# DM3370_IMX214.net
KiCad netlist of a schematic drawn in Altium Designer
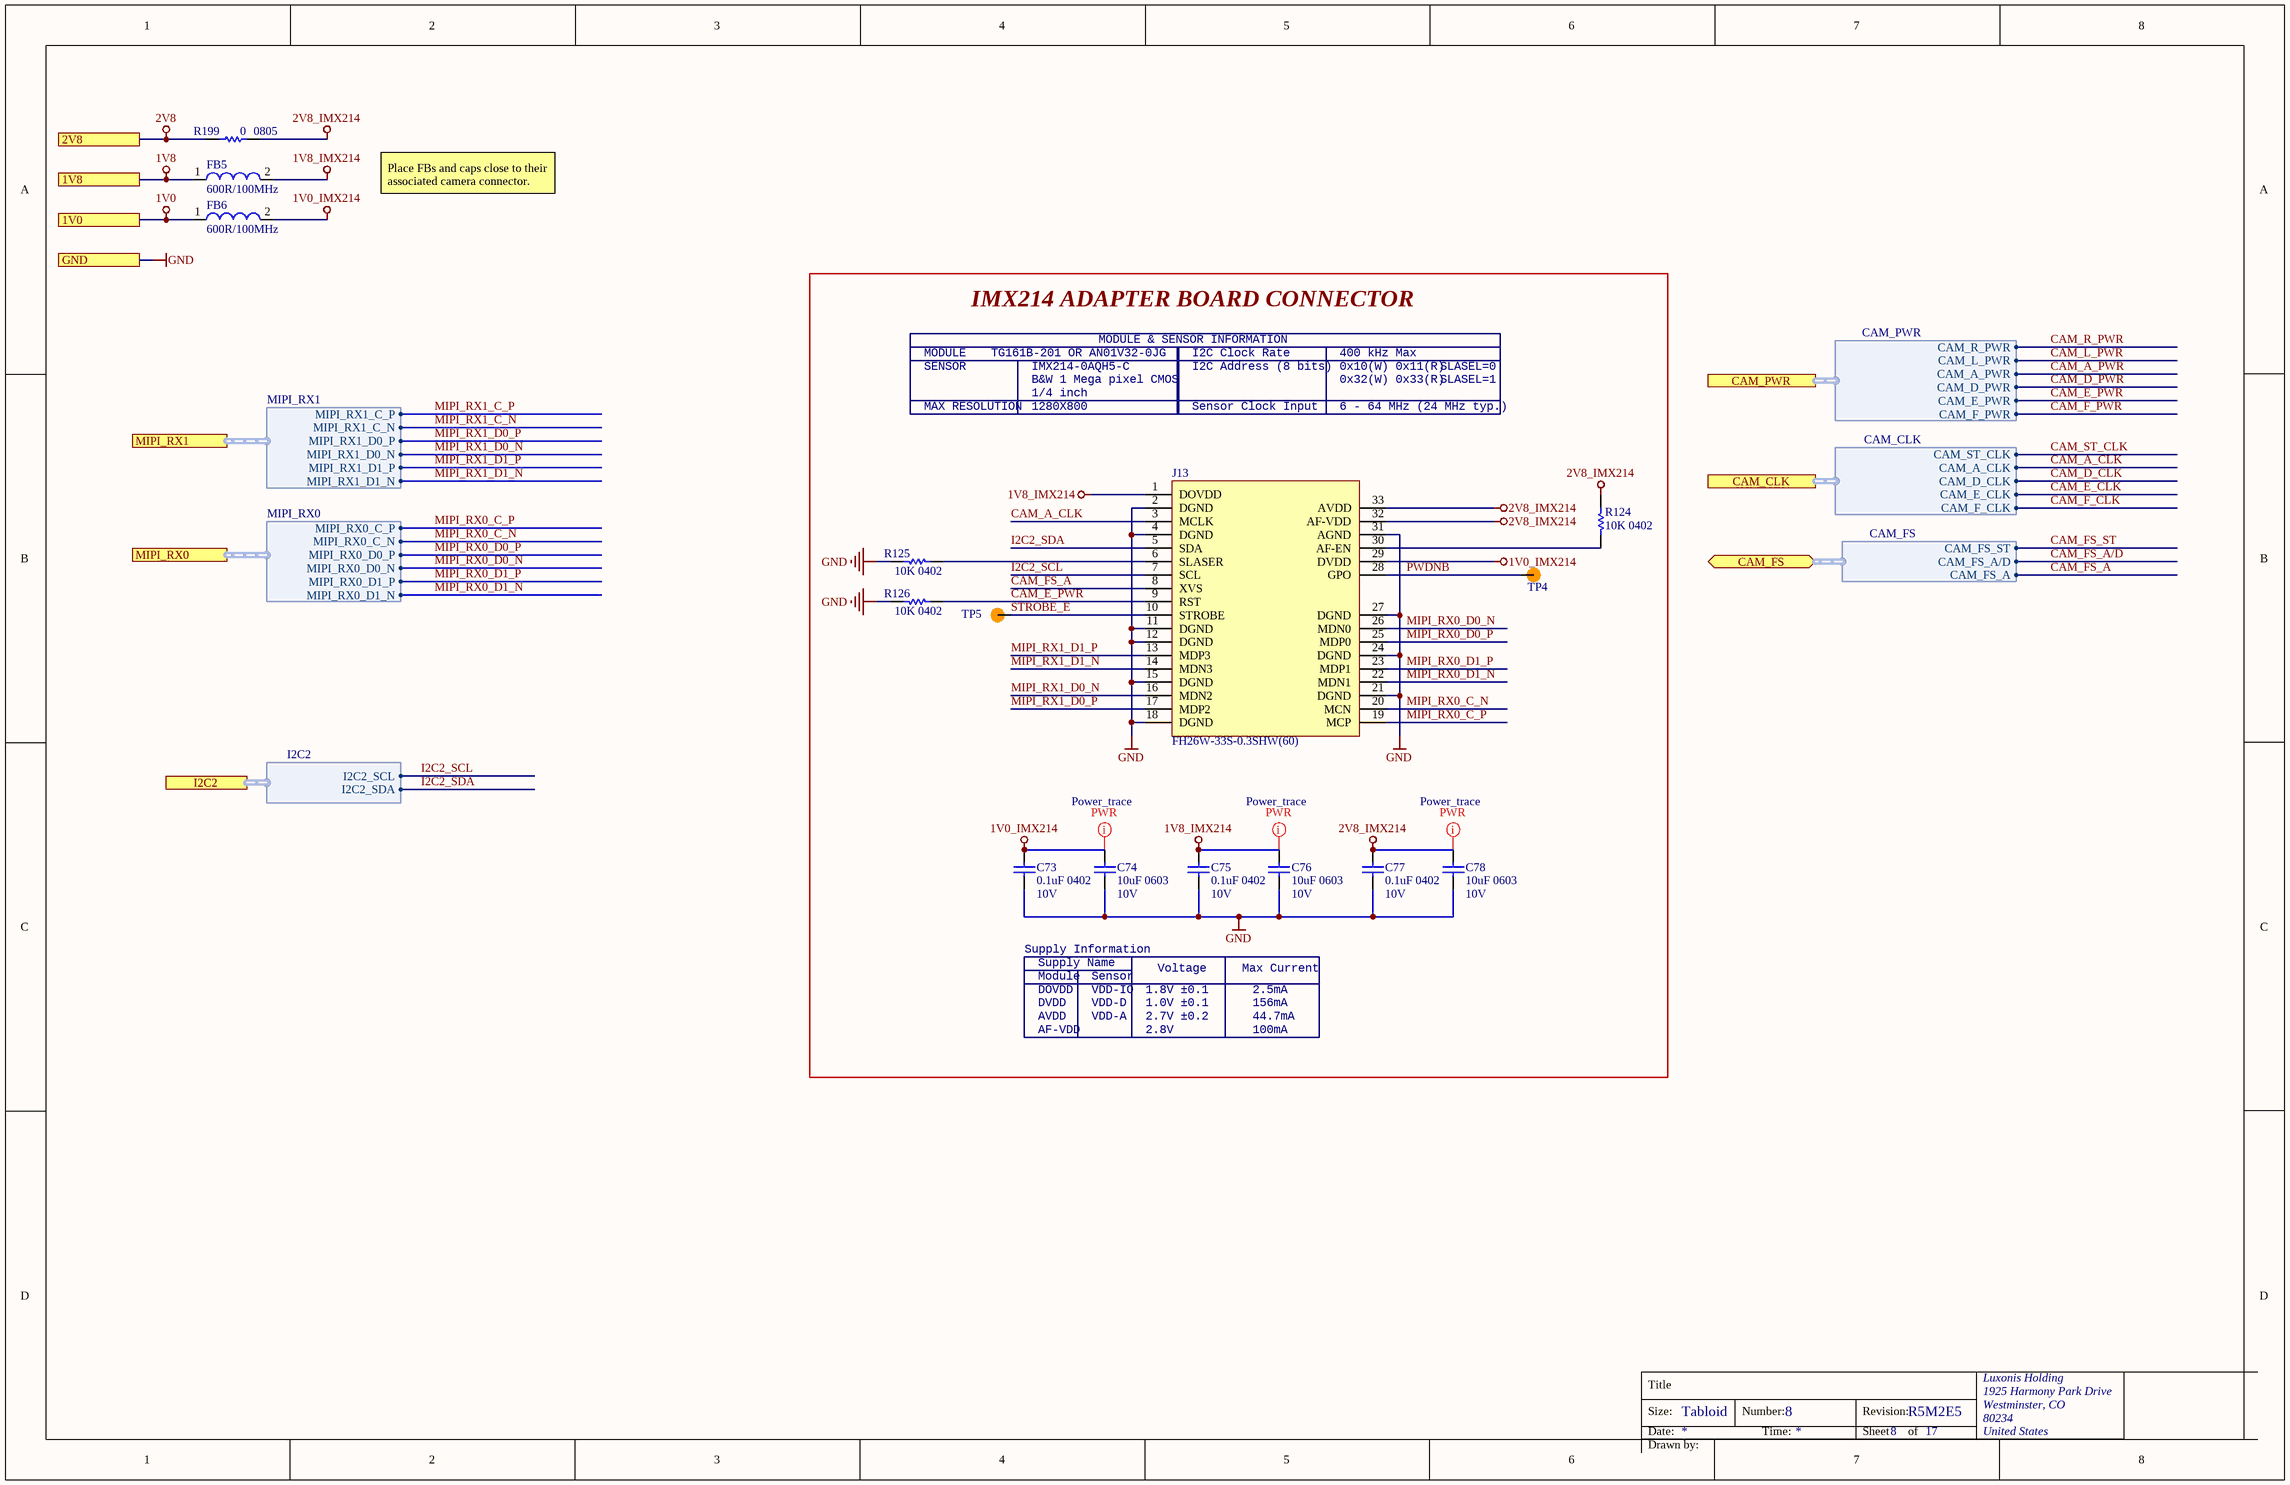
[diagram p0: DM3370_IMX214.SchDoc]

(export (version "E")
  (design (tool "Eeschema 10.0.6"))
  (components
    (comp (ref "C73")
      (value "0.1uF 0402")
      (footprint "CAP_Altium_Vault_Generic:CAPC0402(1005)70_L")
      (description "CAP CER 0.1UF 10V X7R 0402 5%")
      (fields (field (name "TOLERANCE") "5%") (field (name "VOLTAGE RATING") "10V"))
      (libsource (lib "LuxonisMaster") (part "GRM155R71A104JA01D"))
    )
    (comp (ref "C74")
      (value "10uF 0603")
      (footprint "CAP_Altium_Vault_Generic:CAPC0603(1608)100_L")
      (description "CAP CER 10UF 10V X5R 0603 20%")
      (fields (field (name "TOLERANCE") "20%") (field (name "VOLTAGE RATING") "10V"))
      (libsource (lib "LuxonisMaster") (part "GRM188R61A106ME69D"))
    )
    (comp (ref "C75")
      (value "0.1uF 0402")
      (footprint "CAP_Altium_Vault_Generic:CAPC0402(1005)70_L")
      (description "CAP CER 0.1UF 10V X7R 0402 5%")
      (fields (field (name "TOLERANCE") "5%") (field (name "VOLTAGE RATING") "10V"))
      (libsource (lib "LuxonisMaster") (part "GRM155R71A104JA01D"))
    )
    (comp (ref "C76")
      (value "10uF 0603")
      (footprint "CAP_Altium_Vault_Generic:CAPC0603(1608)100_L")
      (description "CAP CER 10UF 10V X5R 0603 20%")
      (fields (field (name "TOLERANCE") "20%") (field (name "VOLTAGE RATING") "10V"))
      (libsource (lib "LuxonisMaster") (part "GRM188R61A106ME69D"))
    )
    (comp (ref "C77")
      (value "0.1uF 0402")
      (footprint "CAP_Altium_Vault_Generic:CAPC0402(1005)70_L")
      (description "CAP CER 0.1UF 10V X7R 0402 5%")
      (fields (field (name "TOLERANCE") "5%") (field (name "VOLTAGE RATING") "10V"))
      (libsource (lib "LuxonisMaster") (part "GRM155R71A104JA01D"))
    )
    (comp (ref "C78")
      (value "10uF 0603")
      (footprint "CAP_Altium_Vault_Generic:CAPC0603(1608)100_L")
      (description "CAP CER 10UF 10V X5R 0603 20%")
      (fields (field (name "TOLERANCE") "20%") (field (name "VOLTAGE RATING") "10V"))
      (libsource (lib "LuxonisMaster") (part "GRM188R61A106ME69D"))
    )
    (comp (ref "FB5")
      (value "600R/100MHz")
      (footprint "LuxonisMaster:2508056017Y2")
      (description "FERRITE BEAD, 0.1OHM, 2A, 0805, 600R/100MHz")
      (fields (field (name "TOLERANCE") "25%"))
      (libsource (lib "LuxonisMaster") (part "2508056017Y2"))
    )
    (comp (ref "FB6")
      (value "600R/100MHz")
      (footprint "LuxonisMaster:2508056017Y2")
      (description "FERRITE BEAD, 0.1OHM, 2A, 0805, 600R/100MHz")
      (fields (field (name "TOLERANCE") "25%"))
      (libsource (lib "LuxonisMaster") (part "2508056017Y2"))
    )
    (comp (ref "J13")
      (value "FH26W-33S-0.3SHW(60)")
      (footprint "FH26W-33S-0.3SHW(60)")
      (description "FFC/FPC Connector, 33 Contact(s), 1 Row(s), Female, Right Angle, Surface Mount Terminal")
      (libsource (lib "Luxonis LLC") (part "FH26W-33S-0.3SHW(60)"))
    )
    (comp (ref "R124")
      (value "10K 0402")
      (footprint "RES_Altium_Vault_Generic:RESC0402(1005)_L")
      (fields (field (name "TOLERANCE") "1%"))
      (libsource (lib "LuxonisMaster") (part "RC0402FR-1310KL"))
    )
    (comp (ref "R125")
      (value "10K 0402")
      (footprint "RES_Altium_Vault_Generic:RESC0402(1005)_L")
      (fields (field (name "TOLERANCE") "1%"))
      (libsource (lib "LuxonisMaster") (part "RC0402FR-1310KL"))
    )
    (comp (ref "R126")
      (value "10K 0402")
      (footprint "RES_Altium_Vault_Generic:RESC0402(1005)_L")
      (fields (field (name "TOLERANCE") "1%"))
      (libsource (lib "LuxonisMaster") (part "RC0402FR-1310KL"))
    )
    (comp (ref "R199")
      (value "0")
      (footprint "RESC0805(2012)_L")
      (description "RES SMD 0 OHM 1% 1/8W 0805")
      (fields (field (name "CASE/PACKAGE") "0805") (field (name "Comment") "CRCW08050000Z0EA"))
      (libsource (lib "Luxonis LLC") (part "Default resistor symbol"))
    )
    (comp (ref "TP4")
      (value "TP100_200_NS")
      (footprint "LuxonisMaster:TP100_200_NS")
      (libsource (lib "LuxonisMaster") (part "TEST_POINT"))
    )
    (comp (ref "TP5")
      (value "TP100_200_NS")
      (footprint "LuxonisMaster:TP100_200_NS")
      (libsource (lib "LuxonisMaster") (part "TEST_POINT"))
    )
  )
  (nets
    (net (code "7") (name "/CAM_A_CLK") (class "Default")
      (node (ref "J13") (pin "3") (pinfunction "MCLK_3") (pintype "passive"))
    )
    (net (code "12") (name "/CAM_E_PWR") (class "Default")
      (node (ref "J13") (pin "9") (pinfunction "RST_9") (pintype "passive"))
      (node (ref "R126") (pin "1") (pinfunction "1_1") (pintype "passive"))
    )
    (net (code "13") (name "/CAM_FS_A") (class "Default")
      (node (ref "J13") (pin "8") (pinfunction "XVS_8") (pintype "passive"))
    )
    (net (code "21") (name "/I2C2_SCL") (class "Default")
      (node (ref "J13") (pin "7") (pinfunction "SCL_7") (pintype "passive"))
    )
    (net (code "22") (name "/I2C2_SDA") (class "Default")
      (node (ref "J13") (pin "5") (pinfunction "SDA_5") (pintype "passive"))
    )
    (net (code "23") (name "/MIPI_RX0_C_N") (class "Default")
      (node (ref "J13") (pin "20") (pinfunction "MCN_20") (pintype "passive"))
    )
    (net (code "24") (name "/MIPI_RX0_C_P") (class "Default")
      (node (ref "J13") (pin "19") (pinfunction "MCP_19") (pintype "passive"))
    )
    (net (code "25") (name "/MIPI_RX0_D0_N") (class "Default")
      (node (ref "J13") (pin "26") (pinfunction "MDN0_26") (pintype "passive"))
    )
    (net (code "26") (name "/MIPI_RX0_D0_P") (class "Default")
      (node (ref "J13") (pin "25") (pinfunction "MDP0_25") (pintype "passive"))
    )
    (net (code "27") (name "/MIPI_RX0_D1_N") (class "Default")
      (node (ref "J13") (pin "22") (pinfunction "MDN1_22") (pintype "passive"))
    )
    (net (code "28") (name "/MIPI_RX0_D1_P") (class "Default")
      (node (ref "J13") (pin "23") (pinfunction "MDP1_23") (pintype "passive"))
    )
    (net (code "31") (name "/MIPI_RX1_D0_N") (class "Default")
      (node (ref "J13") (pin "16") (pinfunction "MDN2_16") (pintype "passive"))
    )
    (net (code "32") (name "/MIPI_RX1_D0_P") (class "Default")
      (node (ref "J13") (pin "17") (pinfunction "MDP2_17") (pintype "passive"))
    )
    (net (code "33") (name "/MIPI_RX1_D1_N") (class "Default")
      (node (ref "J13") (pin "14") (pinfunction "MDN3_14") (pintype "passive"))
    )
    (net (code "34") (name "/MIPI_RX1_D1_P") (class "Default")
      (node (ref "J13") (pin "13") (pinfunction "MDP3_13") (pintype "passive"))
    )
    (net (code "35") (name "/PWDNB") (class "Default")
      (node (ref "J13") (pin "28") (pinfunction "GPO_28") (pintype "passive"))
      (node (ref "TP4") (pin "1") (pintype "passive"))
    )
    (net (code "36") (name "/STROBE_E") (class "Default")
      (node (ref "J13") (pin "10") (pinfunction "STROBE_10") (pintype "passive"))
      (node (ref "TP5") (pin "1") (pintype "passive"))
    )
    (net (code "43") (name "1V0") (class "Default")
      (node (ref "FB6") (pin "1") (pinfunction "1_1") (pintype "passive"))
    )
    (net (code "44") (name "1V0_IMX214") (class "Default")
      (node (ref "C73") (pin "2") (pinfunction "2_2") (pintype "passive"))
      (node (ref "C74") (pin "2") (pinfunction "2_2") (pintype "passive"))
      (node (ref "FB6") (pin "2") (pinfunction "2_2") (pintype "passive"))
      (node (ref "J13") (pin "29") (pinfunction "DVDD_29") (pintype "passive"))
    )
    (net (code "45") (name "1V8") (class "Default")
      (node (ref "FB5") (pin "1") (pinfunction "1_1") (pintype "passive"))
    )
    (net (code "46") (name "1V8_IMX214") (class "Default")
      (node (ref "C75") (pin "2") (pinfunction "2_2") (pintype "passive"))
      (node (ref "C76") (pin "2") (pinfunction "2_2") (pintype "passive"))
      (node (ref "FB5") (pin "2") (pinfunction "2_2") (pintype "passive"))
      (node (ref "J13") (pin "1") (pinfunction "DOVDD_1") (pintype "passive"))
    )
    (net (code "47") (name "2V8") (class "Default")
      (node (ref "R199") (pin "1") (pinfunction "1_1") (pintype "passive"))
    )
    (net (code "48") (name "2V8_IMX214") (class "Default")
      (node (ref "C77") (pin "2") (pinfunction "2_2") (pintype "passive"))
      (node (ref "C78") (pin "2") (pinfunction "2_2") (pintype "passive"))
      (node (ref "J13") (pin "32") (pinfunction "AF-VDD_32") (pintype "passive"))
      (node (ref "J13") (pin "33") (pinfunction "AVDD_33") (pintype "passive"))
      (node (ref "R124") (pin "1") (pinfunction "1_1") (pintype "passive"))
      (node (ref "R199") (pin "2") (pinfunction "2_2") (pintype "passive"))
    )
    (net (code "49") (name "GND") (class "Default")
      (node (ref "C73") (pin "1") (pinfunction "1_1") (pintype "passive"))
      (node (ref "C74") (pin "1") (pinfunction "1_1") (pintype "passive"))
      (node (ref "C75") (pin "1") (pinfunction "1_1") (pintype "passive"))
      (node (ref "C76") (pin "1") (pinfunction "1_1") (pintype "passive"))
      (node (ref "C77") (pin "1") (pinfunction "1_1") (pintype "passive"))
      (node (ref "C78") (pin "1") (pinfunction "1_1") (pintype "passive"))
      (node (ref "J13") (pin "11") (pinfunction "DGND_11") (pintype "passive"))
      (node (ref "J13") (pin "12") (pinfunction "DGND_12") (pintype "passive"))
      (node (ref "J13") (pin "15") (pinfunction "DGND_15") (pintype "passive"))
      (node (ref "J13") (pin "18") (pinfunction "DGND_18") (pintype "passive"))
      (node (ref "J13") (pin "2") (pinfunction "DGND_2") (pintype "passive"))
      (node (ref "J13") (pin "21") (pinfunction "DGND_21") (pintype "passive"))
      (node (ref "J13") (pin "24") (pinfunction "DGND_24") (pintype "passive"))
      (node (ref "J13") (pin "27") (pinfunction "DGND_27") (pintype "passive"))
      (node (ref "J13") (pin "31") (pinfunction "AGND_31") (pintype "passive"))
      (node (ref "J13") (pin "4") (pinfunction "DGND_4") (pintype "passive"))
      (node (ref "R125") (pin "2") (pinfunction "2_2") (pintype "passive"))
      (node (ref "R126") (pin "2") (pinfunction "2_2") (pintype "passive"))
    )
    (net (code "50") (name "Net-(J13-AF-EN)") (class "Default")
      (node (ref "J13") (pin "30") (pinfunction "AF-EN_30") (pintype "passive"))
      (node (ref "R124") (pin "2") (pinfunction "2_2") (pintype "passive"))
    )
    (net (code "51") (name "Net-(J13-SLASER)") (class "Default")
      (node (ref "J13") (pin "6") (pinfunction "SLASER_6") (pintype "passive"))
      (node (ref "R125") (pin "1") (pinfunction "1_1") (pintype "passive"))
    )
  )
)
